# motor_control.net
KiCad netlist of a schematic drawn in Altium Designer
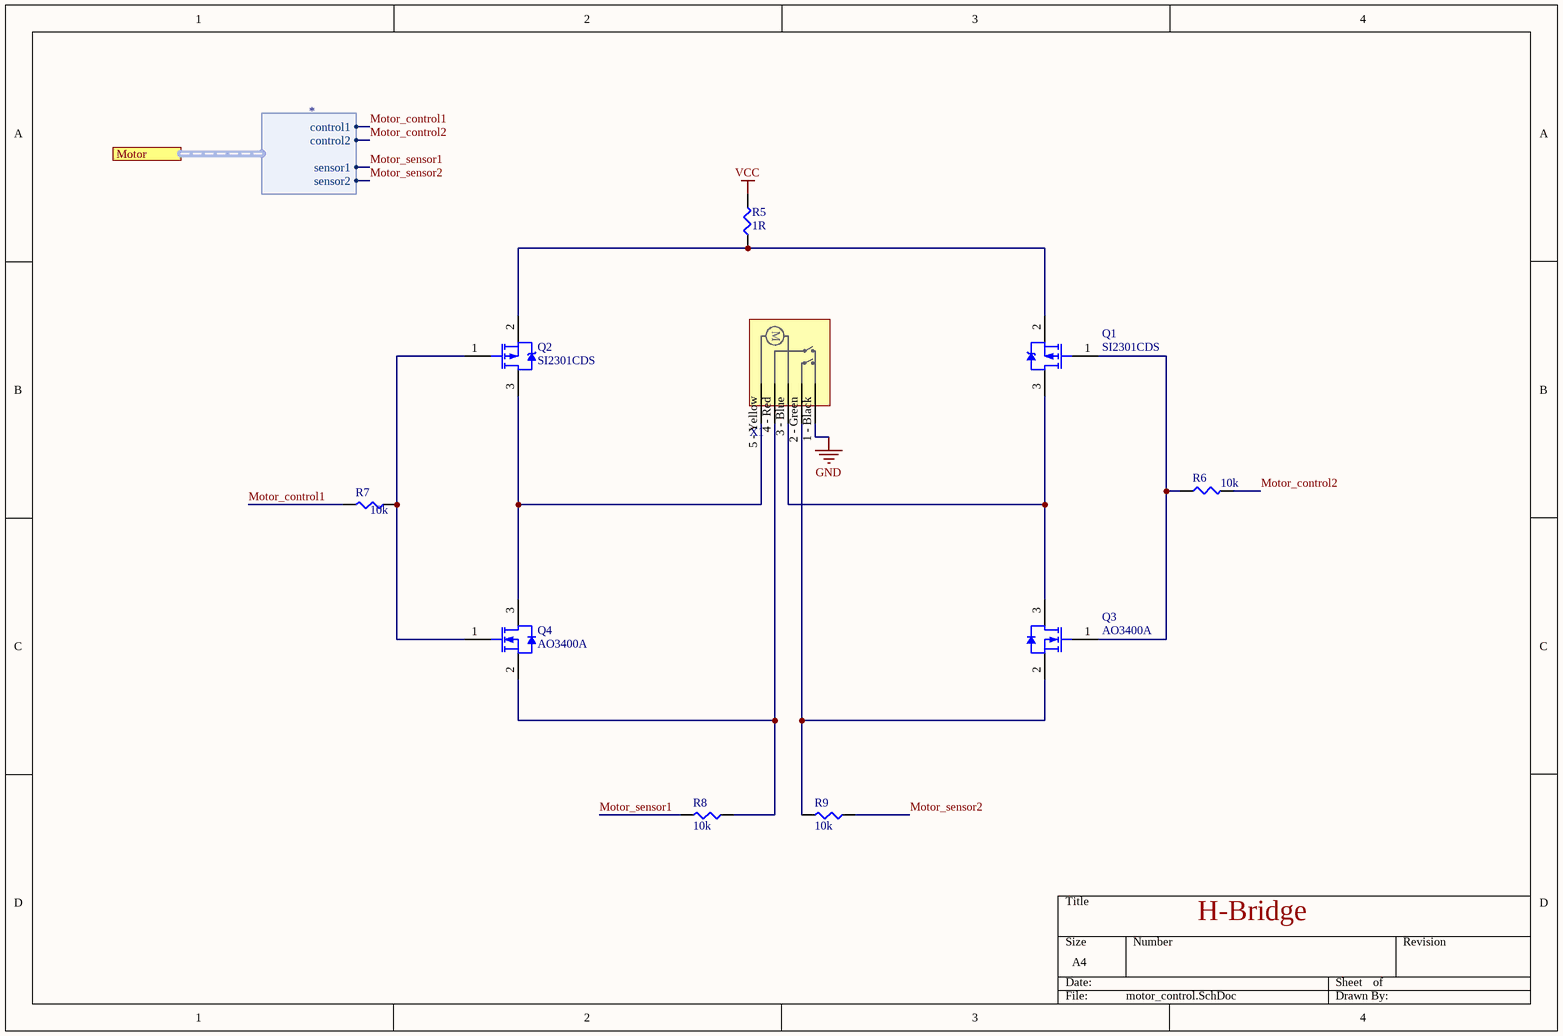
[diagram p0: motor_control.SchDoc]

(export (version "E")
  (design (tool "Eeschema 10.0.6"))
  (components
    (comp (ref "Q1")
      (value "SI2301CDS")
      (footprint "SOT23-3P95_240X114L20X40N")
      (description "P-FET")
      (fields (field (name "LCSC PART #") "C10487"))
      (libsource (lib "WateringSystem_lib") (part "P-FET"))
    )
    (comp (ref "Q2")
      (value "SI2301CDS")
      (footprint "SOT23-3P95_240X114L20X40N")
      (description "P-FET")
      (fields (field (name "LCSC PART #") "C10487"))
      (libsource (lib "WateringSystem_lib") (part "P-FET"))
    )
    (comp (ref "Q3")
      (value "AO3400A")
      (footprint "SOT23-3P95_240X114L20X40N")
      (description "N-FET")
      (fields (field (name "LCSC PART #") "C20917"))
      (libsource (lib "WateringSystem_lib") (part "N-FET"))
    )
    (comp (ref "Q4")
      (value "AO3400A")
      (footprint "SOT23-3P95_240X114L20X40N")
      (description "N-FET")
      (fields (field (name "LCSC PART #") "C20917"))
      (libsource (lib "WateringSystem_lib") (part "N-FET"))
    )
    (comp (ref "R5")
      (value "1R")
      (footprint "RESC200X125X70L40N")
      (fields (field (name "LCSC PART #") "C25271"))
      (libsource (lib "WateringSystem_lib") (part "Resistor"))
    )
    (comp (ref "R6")
      (value "10k")
      (footprint "RESC200X125X70L40N")
      (fields (field (name "LCSC PART #") "C17414"))
      (libsource (lib "WateringSystem_lib") (part "Resistor"))
    )
    (comp (ref "R7")
      (value "10k")
      (footprint "RESC200X125X70L40N")
      (fields (field (name "LCSC PART #") "C17414"))
      (libsource (lib "WateringSystem_lib") (part "Resistor"))
    )
    (comp (ref "R8")
      (value "10k")
      (footprint "RESC200X125X70L40N")
      (fields (field (name "LCSC PART #") "C17414"))
      (libsource (lib "WateringSystem_lib") (part "Resistor"))
    )
    (comp (ref "R9")
      (value "10k")
      (footprint "RESC200X125X70L40N")
      (fields (field (name "LCSC PART #") "C17414"))
      (libsource (lib "WateringSystem_lib") (part "Resistor"))
    )
    (comp (ref "X1")
      (value "motor_connector")
      (footprint "motor_connector")
      (libsource (lib "WateringSystem_lib") (part "motor_connector"))
    )
  )
  (nets
    (net (code "2") (name "/Motor_control1") (class "Default")
      (node (ref "R7") (pin "2") (pinfunction "2_2") (pintype "passive"))
    )
    (net (code "3") (name "/Motor_control2") (class "Default")
      (node (ref "R6") (pin "2") (pinfunction "2_2") (pintype "passive"))
    )
    (net (code "4") (name "/Motor_sensor1") (class "Default")
      (node (ref "R8") (pin "2") (pinfunction "2_2") (pintype "passive"))
    )
    (net (code "5") (name "/Motor_sensor2") (class "Default")
      (node (ref "R9") (pin "1") (pinfunction "1_1") (pintype "passive"))
    )
    (net (code "7") (name "GND") (class "Default")
      (node (ref "X1") (pin "1_-_Black") (pinfunction "1_1_-_Black") (pintype "passive"))
    )
    (net (code "8") (name "Net-(Q1-D)") (class "Default")
      (node (ref "Q1") (pin "3") (pinfunction "D_3") (pintype "passive"))
      (node (ref "Q3") (pin "3") (pinfunction "DRAIN_3") (pintype "passive"))
      (node (ref "X1") (pin "3_-_Blue") (pinfunction "3_3_-_Blue") (pintype "passive"))
    )
    (net (code "9") (name "Net-(Q1-G)") (class "Default")
      (node (ref "Q1") (pin "1") (pinfunction "G_1") (pintype "passive"))
      (node (ref "Q3") (pin "1") (pinfunction "GATE_1") (pintype "passive"))
      (node (ref "R6") (pin "1") (pinfunction "1_1") (pintype "passive"))
    )
    (net (code "10") (name "Net-(Q1-S)") (class "Default")
      (node (ref "Q1") (pin "2") (pinfunction "S_2") (pintype "passive"))
      (node (ref "Q2") (pin "2") (pinfunction "S_2") (pintype "passive"))
      (node (ref "R5") (pin "1") (pinfunction "1_1") (pintype "passive"))
    )
    (net (code "11") (name "Net-(Q2-D)") (class "Default")
      (node (ref "Q2") (pin "3") (pinfunction "D_3") (pintype "passive"))
      (node (ref "Q4") (pin "3") (pinfunction "DRAIN_3") (pintype "passive"))
      (node (ref "X1") (pin "5_-_Yellow") (pinfunction "5_5_-_Yellow") (pintype "passive"))
    )
    (net (code "12") (name "Net-(Q2-G)") (class "Default")
      (node (ref "Q2") (pin "1") (pinfunction "G_1") (pintype "passive"))
      (node (ref "Q4") (pin "1") (pinfunction "GATE_1") (pintype "passive"))
      (node (ref "R7") (pin "1") (pinfunction "1_1") (pintype "passive"))
    )
    (net (code "13") (name "Net-(Q3-SOURCE)") (class "Default")
      (node (ref "Q3") (pin "2") (pinfunction "SOURCE_2") (pintype "passive"))
      (node (ref "R9") (pin "2") (pinfunction "2_2") (pintype "passive"))
      (node (ref "X1") (pin "2_-_Green") (pinfunction "2_2_-_Green") (pintype "passive"))
    )
    (net (code "14") (name "Net-(Q4-SOURCE)") (class "Default")
      (node (ref "Q4") (pin "2") (pinfunction "SOURCE_2") (pintype "passive"))
      (node (ref "R8") (pin "1") (pinfunction "1_1") (pintype "passive"))
      (node (ref "X1") (pin "4_-_Red") (pinfunction "4_4_-_Red") (pintype "passive"))
    )
    (net (code "15") (name "VCC") (class "Default")
      (node (ref "R5") (pin "2") (pinfunction "2_2") (pintype "passive"))
    )
  )
)
